# Steuerung.net
KiCad netlist of a schematic drawn in EAGLE
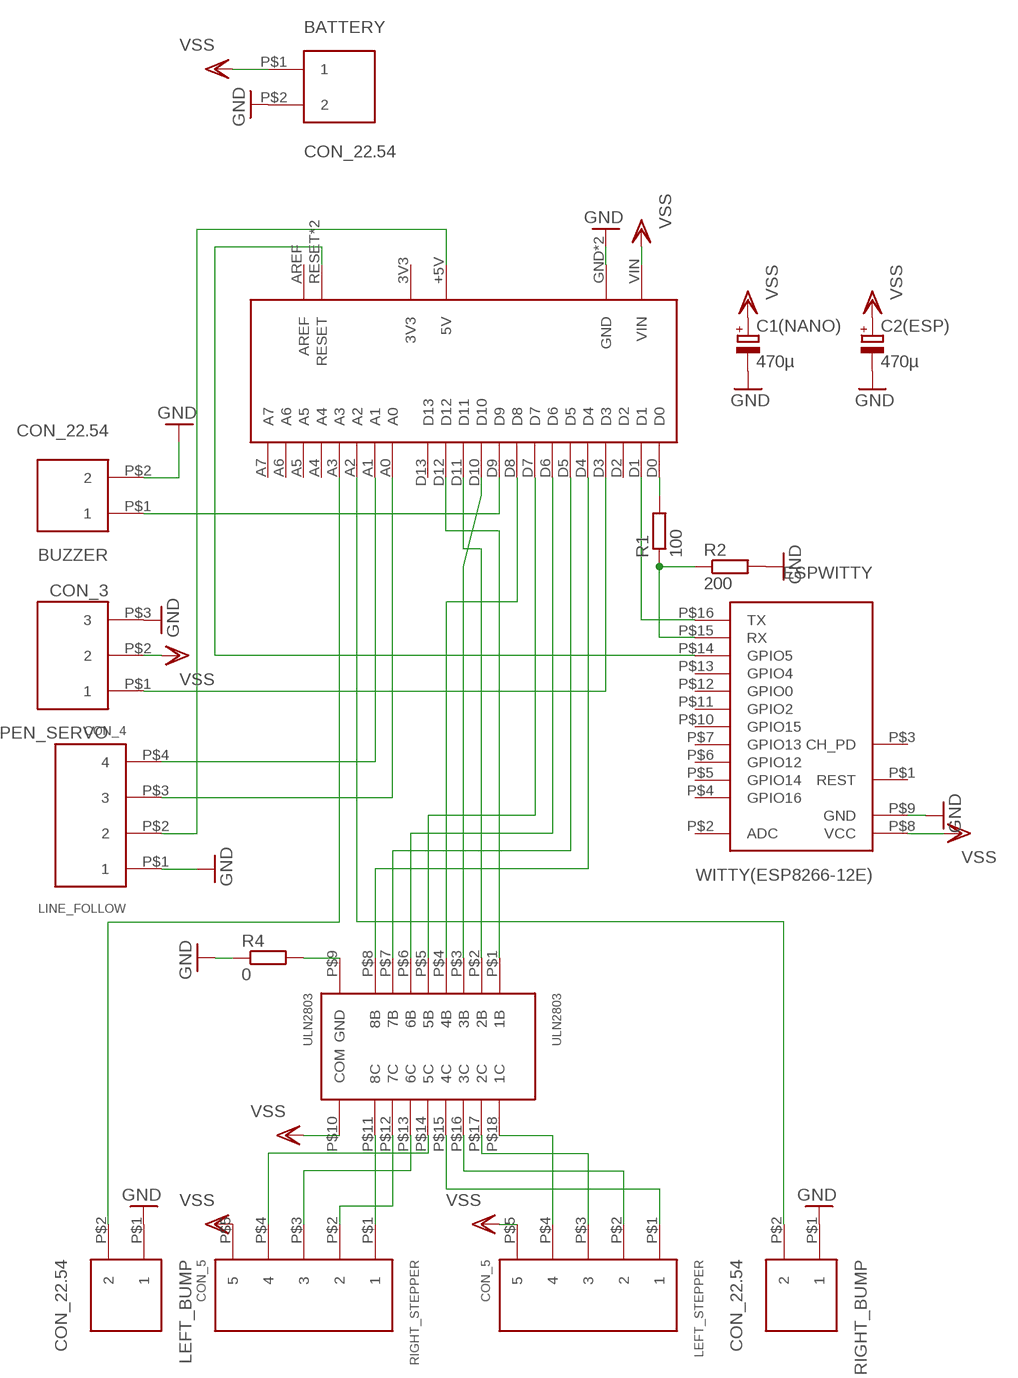
[diagram p0: schematic, sheet 1]

(export (version "E")
  (design (tool "Eeschema 10.0.6"))
  (components
    (comp (ref "ARDUINO_NANO")
      (value "ARDUINO_NANO")
      (footprint "eagle-import:ARDUINO_NANO")
      (libsource (lib "eagle-import") (part "ARDUINO_NANO"))
    )
    (comp (ref "BATTERY")
      (value "CON_22.54")
      (footprint "eagle-import:CON_2_2.54")
      (libsource (lib "eagle-import") (part "CON_22.54"))
    )
    (comp (ref "BUZZER")
      (value "CON_22.54")
      (footprint "eagle-import:CON_2_2.54")
      (libsource (lib "eagle-import") (part "CON_22.54"))
    )
    (comp (ref "C1(NANO)")
      (value "470µ")
      (footprint "eagle-import:E2,5-7")
      (libsource (lib "eagle-import") (part "CPOL-EUE2.5-7"))
    )
    (comp (ref "C2(ESP)")
      (value "470µ")
      (footprint "eagle-import:E2,5-7")
      (libsource (lib "eagle-import") (part "CPOL-EUE2.5-7"))
    )
    (comp (ref "LEFT_BUMP")
      (value "CON_22.54")
      (footprint "eagle-import:CON_2_2.54")
      (libsource (lib "eagle-import") (part "CON_22.54"))
    )
    (comp (ref "LEFT_STEPPER")
      (value "CON_5")
      (footprint "eagle-import:CON_5_2.54")
      (libsource (lib "eagle-import") (part "CON_5"))
    )
    (comp (ref "LINE_FOLLOW")
      (value "CON_4")
      (footprint "eagle-import:CON_4_2.54")
      (libsource (lib "eagle-import") (part "CON_4"))
    )
    (comp (ref "PEN_SERVO")
      (value "CON_3")
      (footprint "eagle-import:CON_3_2.54")
      (libsource (lib "eagle-import") (part "CON_3"))
    )
    (comp (ref "R1")
      (value "100")
      (footprint "eagle-import:0204_7")
      (libsource (lib "eagle-import") (part "resistor_R-EU_0204/7"))
    )
    (comp (ref "R2")
      (value "200")
      (footprint "eagle-import:0204_7")
      (libsource (lib "eagle-import") (part "resistor_R-EU_0204/7"))
    )
    (comp (ref "R4")
      (value "0")
      (footprint "eagle-import:R1206")
      (libsource (lib "eagle-import") (part "R-EU_R1206"))
    )
    (comp (ref "RIGHT_BUMP")
      (value "CON_22.54")
      (footprint "eagle-import:CON_2_2.54")
      (libsource (lib "eagle-import") (part "CON_22.54"))
    )
    (comp (ref "RIGHT_STEPPER")
      (value "CON_5")
      (footprint "eagle-import:CON_5_2.54")
      (libsource (lib "eagle-import") (part "CON_5"))
    )
    (comp (ref "ULN2803")
      (value "ULN2803")
      (footprint "eagle-import:DIP_18")
      (libsource (lib "eagle-import") (part "ULN2803"))
    )
    (comp (ref "WITTY(ESP8266-12E)")
      (value "ESPWITTY")
      (footprint "eagle-import:ESP-WITTY")
      (libsource (lib "eagle-import") (part "ESPWITTY"))
    )
  )
  (nets
    (net (code "1") (name "GND") (class "Default")
      (node (ref "ARDUINO_NANO") (pin "GND") (pinfunction "GND_GND") (pintype "bidirectional"))
      (node (ref "ARDUINO_NANO") (pin "GND2") (pinfunction "GND_GND2") (pintype "bidirectional"))
      (node (ref "BATTERY") (pin "P$2") (pinfunction "2_P$2") (pintype "bidirectional"))
      (node (ref "BUZZER") (pin "P$2") (pinfunction "2_P$2") (pintype "bidirectional"))
      (node (ref "C1(NANO)") (pin "-") (pinfunction "-_-") (pintype "passive"))
      (node (ref "C2(ESP)") (pin "-") (pinfunction "-_-") (pintype "passive"))
      (node (ref "LEFT_BUMP") (pin "P$1") (pinfunction "1_P$1") (pintype "bidirectional"))
      (node (ref "LINE_FOLLOW") (pin "P$1") (pinfunction "1_P$1") (pintype "bidirectional"))
      (node (ref "PEN_SERVO") (pin "P$3") (pinfunction "3_P$3") (pintype "bidirectional"))
      (node (ref "R2") (pin "2") (pinfunction "2_2") (pintype "passive"))
      (node (ref "R4") (pin "1") (pinfunction "1_1") (pintype "passive"))
      (node (ref "RIGHT_BUMP") (pin "P$1") (pinfunction "1_P$1") (pintype "bidirectional"))
      (node (ref "WITTY(ESP8266-12E)") (pin "P$9") (pinfunction "GND_P$9") (pintype "bidirectional"))
    )
    (net (code "2") (name "Net-(ARDUINO_NANO-5V)") (class "Default")
      (node (ref "ARDUINO_NANO") (pin "+5V") (pinfunction "5V_+5V") (pintype "bidirectional"))
      (node (ref "LINE_FOLLOW") (pin "P$2") (pinfunction "2_P$2") (pintype "bidirectional"))
    )
    (net (code "3") (name "Net-(ARDUINO_NANO-PadD0)") (class "Default")
      (node (ref "ARDUINO_NANO") (pin "D0") (pinfunction "D0_D0") (pintype "bidirectional"))
      (node (ref "R1") (pin "2") (pinfunction "2_2") (pintype "passive"))
    )
    (net (code "4") (name "Net-(BUZZER-1)") (class "Default")
      (node (ref "ARDUINO_NANO") (pin "D9") (pinfunction "D9_D9") (pintype "bidirectional"))
      (node (ref "BUZZER") (pin "P$1") (pinfunction "1_P$1") (pintype "bidirectional"))
    )
    (net (code "5") (name "Net-(LEFT_BUMP-2)") (class "Default")
      (node (ref "ARDUINO_NANO") (pin "A3") (pinfunction "A3_A3") (pintype "bidirectional"))
      (node (ref "LEFT_BUMP") (pin "P$2") (pinfunction "2_P$2") (pintype "bidirectional"))
    )
    (net (code "6") (name "Net-(LEFT_STEPPER-1)") (class "Default")
      (node (ref "LEFT_STEPPER") (pin "P$1") (pinfunction "1_P$1") (pintype "bidirectional"))
      (node (ref "ULN2803") (pin "P$15") (pinfunction "4C_P$15") (pintype "bidirectional"))
    )
    (net (code "7") (name "Net-(LEFT_STEPPER-2)") (class "Default")
      (node (ref "LEFT_STEPPER") (pin "P$2") (pinfunction "2_P$2") (pintype "bidirectional"))
      (node (ref "ULN2803") (pin "P$16") (pinfunction "3C_P$16") (pintype "bidirectional"))
    )
    (net (code "8") (name "Net-(LEFT_STEPPER-3)") (class "Default")
      (node (ref "LEFT_STEPPER") (pin "P$3") (pinfunction "3_P$3") (pintype "bidirectional"))
      (node (ref "ULN2803") (pin "P$17") (pinfunction "2C_P$17") (pintype "bidirectional"))
    )
    (net (code "9") (name "Net-(LEFT_STEPPER-4)") (class "Default")
      (node (ref "LEFT_STEPPER") (pin "P$4") (pinfunction "4_P$4") (pintype "bidirectional"))
      (node (ref "ULN2803") (pin "P$18") (pinfunction "1C_P$18") (pintype "bidirectional"))
    )
    (net (code "10") (name "Net-(LINE_FOLLOW-3)") (class "Default")
      (node (ref "ARDUINO_NANO") (pin "A0") (pinfunction "A0_A0") (pintype "bidirectional"))
      (node (ref "LINE_FOLLOW") (pin "P$3") (pinfunction "3_P$3") (pintype "bidirectional"))
    )
    (net (code "11") (name "Net-(LINE_FOLLOW-4)") (class "Default")
      (node (ref "ARDUINO_NANO") (pin "A1") (pinfunction "A1_A1") (pintype "bidirectional"))
      (node (ref "LINE_FOLLOW") (pin "P$4") (pinfunction "4_P$4") (pintype "bidirectional"))
    )
    (net (code "12") (name "Net-(PEN_SERVO-1)") (class "Default")
      (node (ref "ARDUINO_NANO") (pin "D3") (pinfunction "D3_D3") (pintype "bidirectional"))
      (node (ref "PEN_SERVO") (pin "P$1") (pinfunction "1_P$1") (pintype "bidirectional"))
    )
    (net (code "13") (name "Net-(RIGHT_BUMP-2)") (class "Default")
      (node (ref "ARDUINO_NANO") (pin "A2") (pinfunction "A2_A2") (pintype "bidirectional"))
      (node (ref "RIGHT_BUMP") (pin "P$2") (pinfunction "2_P$2") (pintype "bidirectional"))
    )
    (net (code "14") (name "Net-(RIGHT_STEPPER-1)") (class "Default")
      (node (ref "RIGHT_STEPPER") (pin "P$1") (pinfunction "1_P$1") (pintype "bidirectional"))
      (node (ref "ULN2803") (pin "P$11") (pinfunction "8C_P$11") (pintype "bidirectional"))
    )
    (net (code "15") (name "Net-(RIGHT_STEPPER-2)") (class "Default")
      (node (ref "RIGHT_STEPPER") (pin "P$2") (pinfunction "2_P$2") (pintype "bidirectional"))
      (node (ref "ULN2803") (pin "P$12") (pinfunction "7C_P$12") (pintype "bidirectional"))
    )
    (net (code "16") (name "Net-(RIGHT_STEPPER-3)") (class "Default")
      (node (ref "RIGHT_STEPPER") (pin "P$3") (pinfunction "3_P$3") (pintype "bidirectional"))
      (node (ref "ULN2803") (pin "P$13") (pinfunction "6C_P$13") (pintype "bidirectional"))
    )
    (net (code "17") (name "Net-(RIGHT_STEPPER-4)") (class "Default")
      (node (ref "RIGHT_STEPPER") (pin "P$4") (pinfunction "4_P$4") (pintype "bidirectional"))
      (node (ref "ULN2803") (pin "P$14") (pinfunction "5C_P$14") (pintype "bidirectional"))
    )
    (net (code "18") (name "Net-(ULN2803-1B)") (class "Default")
      (node (ref "ARDUINO_NANO") (pin "D12") (pinfunction "D12_D12") (pintype "bidirectional"))
      (node (ref "ULN2803") (pin "P$1") (pinfunction "1B_P$1") (pintype "bidirectional"))
    )
    (net (code "19") (name "Net-(ULN2803-2B)") (class "Default")
      (node (ref "ARDUINO_NANO") (pin "D11") (pinfunction "D11_D11") (pintype "bidirectional"))
      (node (ref "ULN2803") (pin "P$2") (pinfunction "2B_P$2") (pintype "bidirectional"))
    )
    (net (code "20") (name "Net-(ULN2803-3B)") (class "Default")
      (node (ref "ARDUINO_NANO") (pin "D10") (pinfunction "D10_D10") (pintype "bidirectional"))
      (node (ref "ULN2803") (pin "P$3") (pinfunction "3B_P$3") (pintype "bidirectional"))
    )
    (net (code "21") (name "Net-(ULN2803-4B)") (class "Default")
      (node (ref "ARDUINO_NANO") (pin "D8") (pinfunction "D8_D8") (pintype "bidirectional"))
      (node (ref "ULN2803") (pin "P$4") (pinfunction "4B_P$4") (pintype "bidirectional"))
    )
    (net (code "22") (name "Net-(ULN2803-5B)") (class "Default")
      (node (ref "ARDUINO_NANO") (pin "D7") (pinfunction "D7_D7") (pintype "bidirectional"))
      (node (ref "ULN2803") (pin "P$5") (pinfunction "5B_P$5") (pintype "bidirectional"))
    )
    (net (code "23") (name "Net-(ULN2803-6B)") (class "Default")
      (node (ref "ARDUINO_NANO") (pin "D6") (pinfunction "D6_D6") (pintype "bidirectional"))
      (node (ref "ULN2803") (pin "P$6") (pinfunction "6B_P$6") (pintype "bidirectional"))
    )
    (net (code "24") (name "Net-(ULN2803-7B)") (class "Default")
      (node (ref "ARDUINO_NANO") (pin "D5") (pinfunction "D5_D5") (pintype "bidirectional"))
      (node (ref "ULN2803") (pin "P$7") (pinfunction "7B_P$7") (pintype "bidirectional"))
    )
    (net (code "25") (name "Net-(ULN2803-8B)") (class "Default")
      (node (ref "ARDUINO_NANO") (pin "D4") (pinfunction "D4_D4") (pintype "bidirectional"))
      (node (ref "ULN2803") (pin "P$8") (pinfunction "8B_P$8") (pintype "bidirectional"))
    )
    (net (code "26") (name "Net-(ULN2803-GND)") (class "Default")
      (node (ref "R4") (pin "2") (pinfunction "2_2") (pintype "passive"))
      (node (ref "ULN2803") (pin "P$9") (pinfunction "GND_P$9") (pintype "bidirectional"))
    )
    (net (code "27") (name "Net-(WITTY(ESP8266-12E)-GPIO5)") (class "Default")
      (node (ref "ARDUINO_NANO") (pin "RESET") (pinfunction "RESET_RESET") (pintype "bidirectional"))
      (node (ref "ARDUINO_NANO") (pin "RST") (pinfunction "RESET_RST") (pintype "bidirectional"))
      (node (ref "WITTY(ESP8266-12E)") (pin "P$14") (pinfunction "GPIO5_P$14") (pintype "bidirectional"))
    )
    (net (code "28") (name "Net-(WITTY(ESP8266-12E)-RX)") (class "Default")
      (node (ref "R1") (pin "1") (pinfunction "1_1") (pintype "passive"))
      (node (ref "R2") (pin "1") (pinfunction "1_1") (pintype "passive"))
      (node (ref "WITTY(ESP8266-12E)") (pin "P$15") (pinfunction "RX_P$15") (pintype "bidirectional"))
    )
    (net (code "29") (name "Net-(WITTY(ESP8266-12E)-TX)") (class "Default")
      (node (ref "ARDUINO_NANO") (pin "D1") (pinfunction "D1_D1") (pintype "bidirectional"))
      (node (ref "WITTY(ESP8266-12E)") (pin "P$16") (pinfunction "TX_P$16") (pintype "bidirectional"))
    )
    (net (code "30") (name "VSS") (class "Default")
      (node (ref "ARDUINO_NANO") (pin "VIN") (pinfunction "VIN_VIN") (pintype "bidirectional"))
      (node (ref "BATTERY") (pin "P$1") (pinfunction "1_P$1") (pintype "bidirectional"))
      (node (ref "C1(NANO)") (pin "+") (pinfunction "+_+") (pintype "passive"))
      (node (ref "C2(ESP)") (pin "+") (pinfunction "+_+") (pintype "passive"))
      (node (ref "LEFT_STEPPER") (pin "P$5") (pinfunction "5_P$5") (pintype "bidirectional"))
      (node (ref "PEN_SERVO") (pin "P$2") (pinfunction "2_P$2") (pintype "bidirectional"))
      (node (ref "RIGHT_STEPPER") (pin "P$5") (pinfunction "5_P$5") (pintype "bidirectional"))
      (node (ref "ULN2803") (pin "P$10") (pinfunction "COM_P$10") (pintype "bidirectional"))
      (node (ref "WITTY(ESP8266-12E)") (pin "P$8") (pinfunction "VCC_P$8") (pintype "bidirectional"))
    )
    (net (code "31") (name "unconnected-(ARDUINO_NANO-Pad3V3)") (class "Default")
      (node (ref "ARDUINO_NANO") (pin "3V3") (pinfunction "3V3_3V3") (pintype "bidirectional"))
    )
    (net (code "32") (name "unconnected-(ARDUINO_NANO-PadA4)") (class "Default")
      (node (ref "ARDUINO_NANO") (pin "A4") (pinfunction "A4_A4") (pintype "bidirectional"))
    )
    (net (code "33") (name "unconnected-(ARDUINO_NANO-PadA5)") (class "Default")
      (node (ref "ARDUINO_NANO") (pin "A5") (pinfunction "A5_A5") (pintype "bidirectional"))
    )
    (net (code "34") (name "unconnected-(ARDUINO_NANO-PadA6)") (class "Default")
      (node (ref "ARDUINO_NANO") (pin "A6") (pinfunction "A6_A6") (pintype "bidirectional"))
    )
    (net (code "35") (name "unconnected-(ARDUINO_NANO-PadA7)") (class "Default")
      (node (ref "ARDUINO_NANO") (pin "A7") (pinfunction "A7_A7") (pintype "bidirectional"))
    )
    (net (code "36") (name "unconnected-(ARDUINO_NANO-PadAREF)") (class "Default")
      (node (ref "ARDUINO_NANO") (pin "AREF") (pinfunction "AREF_AREF") (pintype "bidirectional"))
    )
    (net (code "37") (name "unconnected-(ARDUINO_NANO-PadD2)") (class "Default")
      (node (ref "ARDUINO_NANO") (pin "D2") (pinfunction "D2_D2") (pintype "bidirectional"))
    )
    (net (code "38") (name "unconnected-(ARDUINO_NANO-PadD13)") (class "Default")
      (node (ref "ARDUINO_NANO") (pin "D13") (pinfunction "D13_D13") (pintype "bidirectional"))
    )
    (net (code "39") (name "unconnected-(WITTY(ESP8266-12E)-ADC-PadP$2)") (class "Default")
      (node (ref "WITTY(ESP8266-12E)") (pin "P$2") (pinfunction "ADC_P$2") (pintype "bidirectional"))
    )
    (net (code "40") (name "unconnected-(WITTY(ESP8266-12E)-CH_PD-PadP$3)") (class "Default")
      (node (ref "WITTY(ESP8266-12E)") (pin "P$3") (pinfunction "CH_PD_P$3") (pintype "bidirectional"))
    )
    (net (code "41") (name "unconnected-(WITTY(ESP8266-12E)-GPIO0-PadP$12)") (class "Default")
      (node (ref "WITTY(ESP8266-12E)") (pin "P$12") (pinfunction "GPIO0_P$12") (pintype "bidirectional"))
    )
    (net (code "42") (name "unconnected-(WITTY(ESP8266-12E)-GPIO2-PadP$11)") (class "Default")
      (node (ref "WITTY(ESP8266-12E)") (pin "P$11") (pinfunction "GPIO2_P$11") (pintype "bidirectional"))
    )
    (net (code "43") (name "unconnected-(WITTY(ESP8266-12E)-GPIO4-PadP$13)") (class "Default")
      (node (ref "WITTY(ESP8266-12E)") (pin "P$13") (pinfunction "GPIO4_P$13") (pintype "bidirectional"))
    )
    (net (code "44") (name "unconnected-(WITTY(ESP8266-12E)-GPIO12-PadP$6)") (class "Default")
      (node (ref "WITTY(ESP8266-12E)") (pin "P$6") (pinfunction "GPIO12_P$6") (pintype "bidirectional"))
    )
    (net (code "45") (name "unconnected-(WITTY(ESP8266-12E)-GPIO13-PadP$7)") (class "Default")
      (node (ref "WITTY(ESP8266-12E)") (pin "P$7") (pinfunction "GPIO13_P$7") (pintype "bidirectional"))
    )
    (net (code "46") (name "unconnected-(WITTY(ESP8266-12E)-GPIO14-PadP$5)") (class "Default")
      (node (ref "WITTY(ESP8266-12E)") (pin "P$5") (pinfunction "GPIO14_P$5") (pintype "bidirectional"))
    )
    (net (code "47") (name "unconnected-(WITTY(ESP8266-12E)-GPIO15-PadP$10)") (class "Default")
      (node (ref "WITTY(ESP8266-12E)") (pin "P$10") (pinfunction "GPIO15_P$10") (pintype "bidirectional"))
    )
    (net (code "48") (name "unconnected-(WITTY(ESP8266-12E)-GPIO16-PadP$4)") (class "Default")
      (node (ref "WITTY(ESP8266-12E)") (pin "P$4") (pinfunction "GPIO16_P$4") (pintype "bidirectional"))
    )
    (net (code "49") (name "unconnected-(WITTY(ESP8266-12E)-REST-PadP$1)") (class "Default")
      (node (ref "WITTY(ESP8266-12E)") (pin "P$1") (pinfunction "REST_P$1") (pintype "bidirectional"))
    )
  )
)
